# M650X.net
KiCad netlist of a schematic drawn in EAGLE
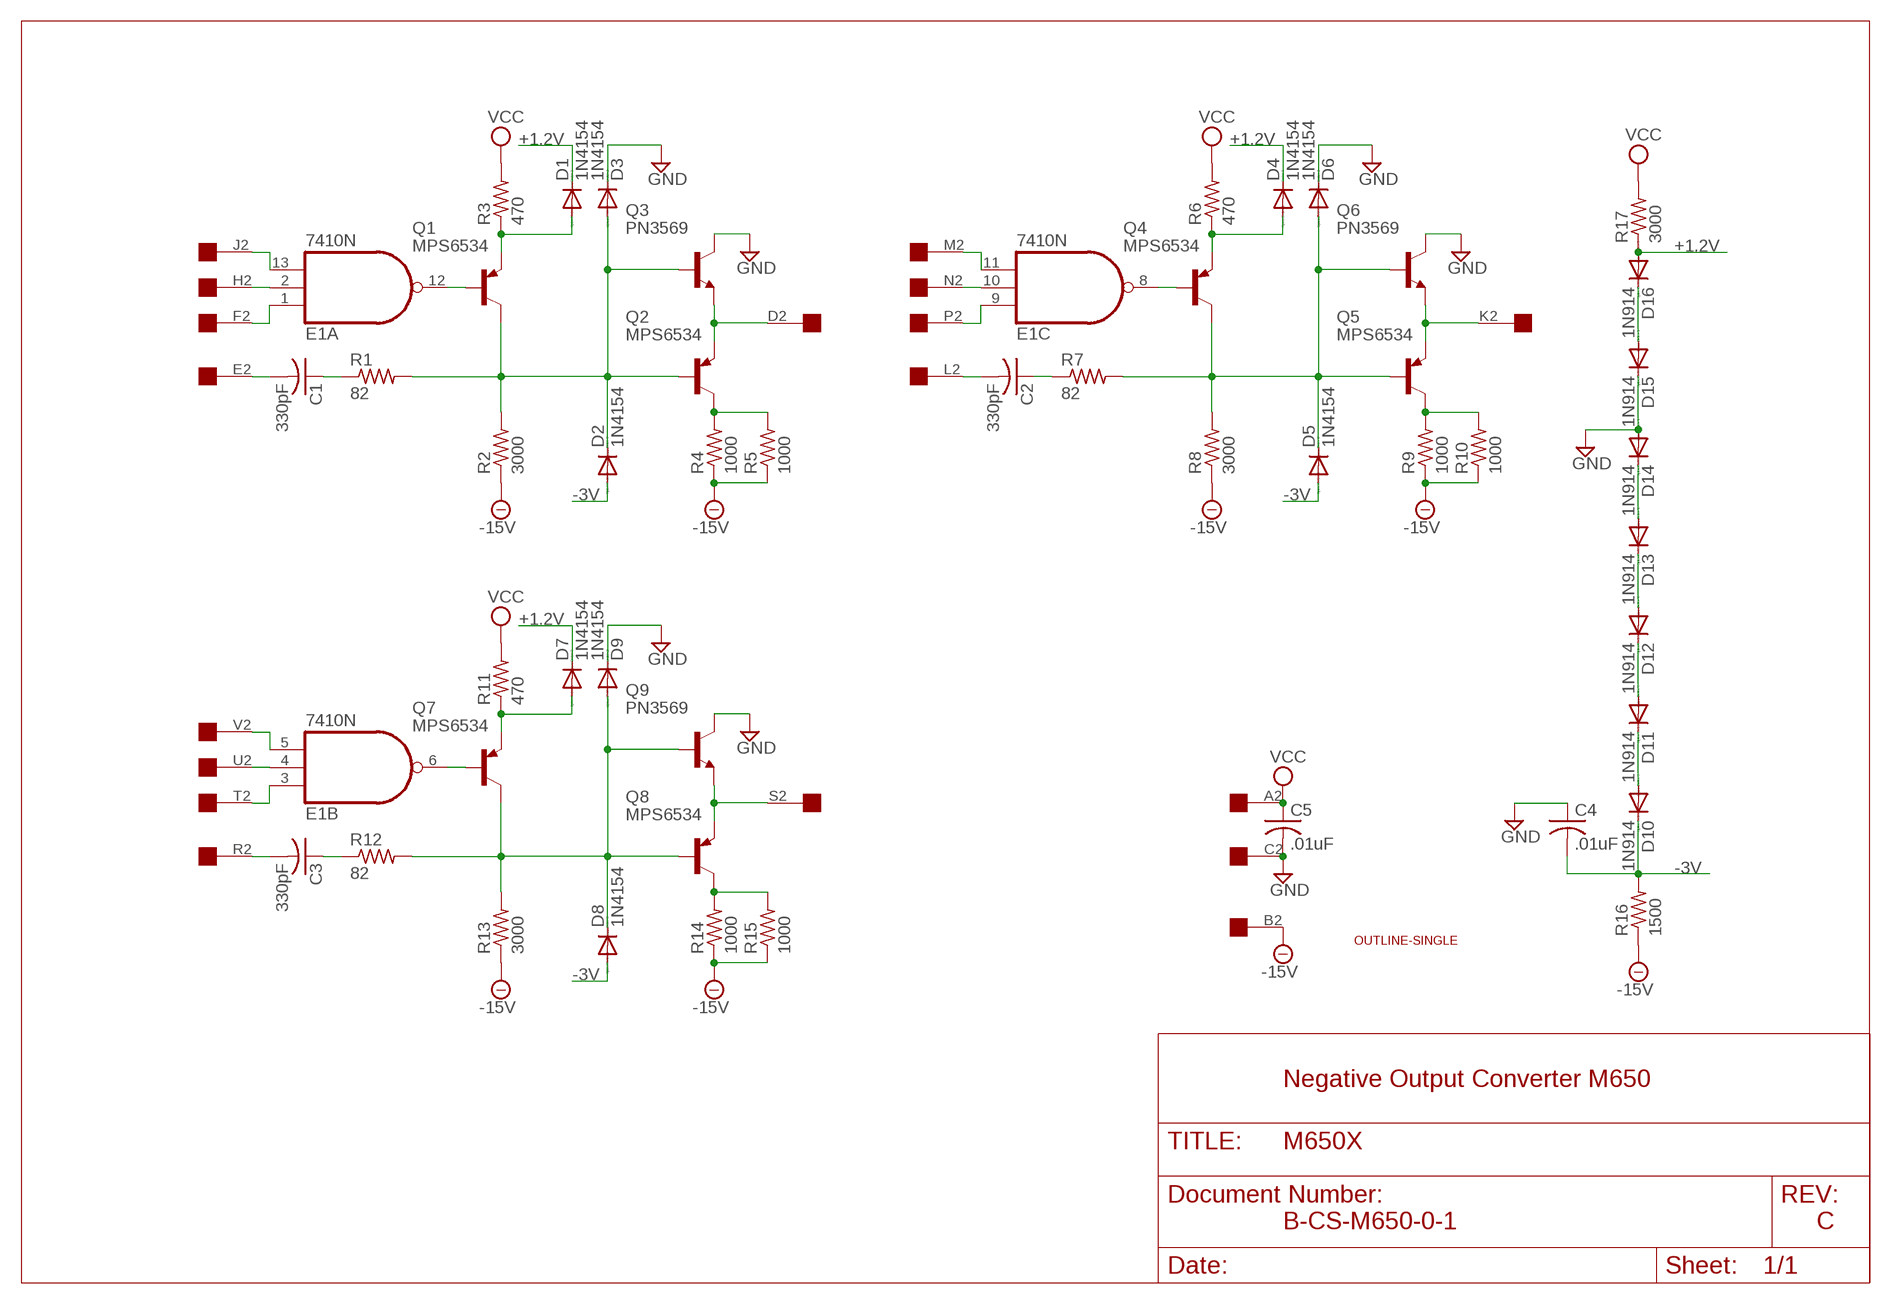
[diagram p0: schematic, sheet 1]

(export (version "E")
  (design (tool "Eeschema 10.0.6"))
  (components
    (comp (ref "C1")
      (value "330pF")
      (footprint "eagle-import:C050-025X075")
      (libsource (lib "eagle-import") (part "C-US050-025X075"))
    )
    (comp (ref "C2")
      (value "330pF")
      (footprint "eagle-import:C050-025X075")
      (libsource (lib "eagle-import") (part "C-US050-025X075"))
    )
    (comp (ref "C3")
      (value "330pF")
      (footprint "eagle-import:C050-025X075")
      (libsource (lib "eagle-import") (part "C-US050-025X075"))
    )
    (comp (ref "C4")
      (value ".01uF")
      (footprint "eagle-import:C050-025X075")
      (libsource (lib "eagle-import") (part "C-US050-025X075"))
    )
    (comp (ref "C5")
      (value ".01uF")
      (footprint "eagle-import:C050-025X075")
      (libsource (lib "eagle-import") (part "C-US050-025X075"))
    )
    (comp (ref "D1")
      (value "1N4154")
      (footprint "eagle-import:DO35-10")
      (libsource (lib "eagle-import") (part "1N4148DO35-10"))
    )
    (comp (ref "D2")
      (value "1N4154")
      (footprint "eagle-import:DO35-10")
      (libsource (lib "eagle-import") (part "1N4148DO35-10"))
    )
    (comp (ref "D3")
      (value "1N4154")
      (footprint "eagle-import:DO35-10")
      (libsource (lib "eagle-import") (part "1N4148DO35-10"))
    )
    (comp (ref "D4")
      (value "1N4154")
      (footprint "eagle-import:DO35-10")
      (libsource (lib "eagle-import") (part "1N4148DO35-10"))
    )
    (comp (ref "D5")
      (value "1N4154")
      (footprint "eagle-import:DO35-10")
      (libsource (lib "eagle-import") (part "1N4148DO35-10"))
    )
    (comp (ref "D6")
      (value "1N4154")
      (footprint "eagle-import:DO35-10")
      (libsource (lib "eagle-import") (part "1N4148DO35-10"))
    )
    (comp (ref "D7")
      (value "1N4154")
      (footprint "eagle-import:DO35-10")
      (libsource (lib "eagle-import") (part "1N4148DO35-10"))
    )
    (comp (ref "D8")
      (value "1N4154")
      (footprint "eagle-import:DO35-10")
      (libsource (lib "eagle-import") (part "1N4148DO35-10"))
    )
    (comp (ref "D9")
      (value "1N4154")
      (footprint "eagle-import:DO35-10")
      (libsource (lib "eagle-import") (part "1N4148DO35-10"))
    )
    (comp (ref "D10")
      (value "1N914")
      (footprint "eagle-import:DO35-10")
      (libsource (lib "eagle-import") (part "1N4148DO35-10"))
    )
    (comp (ref "D11")
      (value "1N914")
      (footprint "eagle-import:DO35-10")
      (libsource (lib "eagle-import") (part "1N4148DO35-10"))
    )
    (comp (ref "D12")
      (value "1N914")
      (footprint "eagle-import:DO35-10")
      (libsource (lib "eagle-import") (part "1N4148DO35-10"))
    )
    (comp (ref "D13")
      (value "1N914")
      (footprint "eagle-import:DO35-10")
      (libsource (lib "eagle-import") (part "1N4148DO35-10"))
    )
    (comp (ref "D14")
      (value "1N914")
      (footprint "eagle-import:DO35-10")
      (libsource (lib "eagle-import") (part "1N4148DO35-10"))
    )
    (comp (ref "D15")
      (value "1N914")
      (footprint "eagle-import:DO35-10")
      (libsource (lib "eagle-import") (part "1N4148DO35-10"))
    )
    (comp (ref "D16")
      (value "1N914")
      (footprint "eagle-import:DO35-10")
      (libsource (lib "eagle-import") (part "1N4148DO35-10"))
    )
    (comp (ref "E1")
      (value "7410N")
      (footprint "eagle-import:DIL14")
      (libsource (lib "eagle-import") (part "7410N"))
    )
    (comp (ref "Q1")
      (value "MPS6534")
      (footprint "eagle-import:TO39")
      (libsource (lib "eagle-import") (part "2N5415"))
    )
    (comp (ref "Q2")
      (value "MPS6534")
      (footprint "eagle-import:TO39")
      (libsource (lib "eagle-import") (part "2N5415"))
    )
    (comp (ref "Q3")
      (value "PN3569")
      (footprint "eagle-import:TO5")
      (libsource (lib "eagle-import") (part "2N2219"))
    )
    (comp (ref "Q4")
      (value "MPS6534")
      (footprint "eagle-import:TO39")
      (libsource (lib "eagle-import") (part "2N5415"))
    )
    (comp (ref "Q5")
      (value "MPS6534")
      (footprint "eagle-import:TO39")
      (libsource (lib "eagle-import") (part "2N5415"))
    )
    (comp (ref "Q6")
      (value "PN3569")
      (footprint "eagle-import:TO5")
      (libsource (lib "eagle-import") (part "2N2219"))
    )
    (comp (ref "Q7")
      (value "MPS6534")
      (footprint "eagle-import:TO39")
      (libsource (lib "eagle-import") (part "2N5415"))
    )
    (comp (ref "Q8")
      (value "MPS6534")
      (footprint "eagle-import:TO39")
      (libsource (lib "eagle-import") (part "2N5415"))
    )
    (comp (ref "Q9")
      (value "PN3569")
      (footprint "eagle-import:TO5")
      (libsource (lib "eagle-import") (part "2N2219"))
    )
    (comp (ref "R1")
      (value "82")
      (footprint "eagle-import:0207_10")
      (libsource (lib "eagle-import") (part "R-US_0207/10"))
    )
    (comp (ref "R2")
      (value "3000")
      (footprint "eagle-import:0207_10")
      (libsource (lib "eagle-import") (part "R-US_0207/10"))
    )
    (comp (ref "R3")
      (value "470")
      (footprint "eagle-import:0207_10")
      (libsource (lib "eagle-import") (part "R-US_0207/10"))
    )
    (comp (ref "R4")
      (value "1000")
      (footprint "eagle-import:0207_10")
      (libsource (lib "eagle-import") (part "R-US_0207/10"))
    )
    (comp (ref "R5")
      (value "1000")
      (footprint "eagle-import:0207_10")
      (libsource (lib "eagle-import") (part "R-US_0207/10"))
    )
    (comp (ref "R6")
      (value "470")
      (footprint "eagle-import:0207_10")
      (libsource (lib "eagle-import") (part "R-US_0207/10"))
    )
    (comp (ref "R7")
      (value "82")
      (footprint "eagle-import:0207_10")
      (libsource (lib "eagle-import") (part "R-US_0207/10"))
    )
    (comp (ref "R8")
      (value "3000")
      (footprint "eagle-import:0207_10")
      (libsource (lib "eagle-import") (part "R-US_0207/10"))
    )
    (comp (ref "R9")
      (value "1000")
      (footprint "eagle-import:0207_10")
      (libsource (lib "eagle-import") (part "R-US_0207/10"))
    )
    (comp (ref "R10")
      (value "1000")
      (footprint "eagle-import:0207_10")
      (libsource (lib "eagle-import") (part "R-US_0207/10"))
    )
    (comp (ref "R11")
      (value "470")
      (footprint "eagle-import:0207_10")
      (libsource (lib "eagle-import") (part "R-US_0207/10"))
    )
    (comp (ref "R12")
      (value "82")
      (footprint "eagle-import:0207_10")
      (libsource (lib "eagle-import") (part "R-US_0207/10"))
    )
    (comp (ref "R13")
      (value "3000")
      (footprint "eagle-import:0207_10")
      (libsource (lib "eagle-import") (part "R-US_0207/10"))
    )
    (comp (ref "R14")
      (value "1000")
      (footprint "eagle-import:0207_10")
      (libsource (lib "eagle-import") (part "R-US_0207/10"))
    )
    (comp (ref "R15")
      (value "1000")
      (footprint "eagle-import:0207_10")
      (libsource (lib "eagle-import") (part "R-US_0207/10"))
    )
    (comp (ref "R16")
      (value "1500")
      (footprint "eagle-import:0207_10")
      (libsource (lib "eagle-import") (part "R-US_0207/10"))
    )
    (comp (ref "R17")
      (value "3000")
      (footprint "eagle-import:0207_10")
      (libsource (lib "eagle-import") (part "R-US_0207/10"))
    )
    (comp (ref "U$1")
      (value "OUTLINE-SINGLE")
      (footprint "eagle-import:SINGLE")
      (libsource (lib "eagle-import") (part "OUTLINE-SINGLE"))
    )
    (comp (ref "U$3")
      (value "EDGE-1")
      (footprint "eagle-import:EDGE-CON1")
      (libsource (lib "eagle-import") (part "EDGE-1"))
    )
  )
  (nets
    (net (code "1") (name "-15V") (class "Default")
      (node (ref "R10") (pin "1") (pinfunction "1_1") (pintype "passive"))
      (node (ref "R13") (pin "1") (pinfunction "1_1") (pintype "passive"))
      (node (ref "R14") (pin "1") (pinfunction "1_1") (pintype "passive"))
      (node (ref "R15") (pin "1") (pinfunction "1_1") (pintype "passive"))
      (node (ref "R16") (pin "1") (pinfunction "1_1") (pintype "passive"))
      (node (ref "R2") (pin "1") (pinfunction "1_1") (pintype "passive"))
      (node (ref "R4") (pin "1") (pinfunction "1_1") (pintype "passive"))
      (node (ref "R5") (pin "1") (pinfunction "1_1") (pintype "passive"))
      (node (ref "R8") (pin "1") (pinfunction "1_1") (pintype "passive"))
      (node (ref "R9") (pin "1") (pinfunction "1_1") (pintype "passive"))
      (node (ref "U$3") (pin "B2") (pinfunction "1_B2") (pintype "bidirectional"))
    )
    (net (code "2") (name "/+1.2V") (class "Default")
      (node (ref "D1") (pin "C") (pinfunction "C_C") (pintype "passive"))
      (node (ref "D16") (pin "A") (pinfunction "A_A") (pintype "passive"))
      (node (ref "D4") (pin "C") (pinfunction "C_C") (pintype "passive"))
      (node (ref "D7") (pin "C") (pinfunction "C_C") (pintype "passive"))
      (node (ref "R17") (pin "1") (pinfunction "1_1") (pintype "passive"))
    )
    (net (code "3") (name "/-3V") (class "Default")
      (node (ref "C4") (pin "2") (pinfunction "2_2") (pintype "passive"))
      (node (ref "D10") (pin "C") (pinfunction "C_C") (pintype "passive"))
      (node (ref "D2") (pin "A") (pinfunction "A_A") (pintype "passive"))
      (node (ref "D5") (pin "A") (pinfunction "A_A") (pintype "passive"))
      (node (ref "D8") (pin "A") (pinfunction "A_A") (pintype "passive"))
      (node (ref "R16") (pin "2") (pinfunction "2_2") (pintype "passive"))
    )
    (net (code "4") (name "GND") (class "Default")
      (node (ref "C4") (pin "1") (pinfunction "1_1") (pintype "passive"))
      (node (ref "C5") (pin "2") (pinfunction "2_2") (pintype "passive"))
      (node (ref "D14") (pin "A") (pinfunction "A_A") (pintype "passive"))
      (node (ref "D15") (pin "C") (pinfunction "C_C") (pintype "passive"))
      (node (ref "D3") (pin "C") (pinfunction "C_C") (pintype "passive"))
      (node (ref "D6") (pin "C") (pinfunction "C_C") (pintype "passive"))
      (node (ref "D9") (pin "C") (pinfunction "C_C") (pintype "passive"))
      (node (ref "Q3") (pin "3") (pinfunction "C_3") (pintype "passive"))
      (node (ref "Q6") (pin "3") (pinfunction "C_3") (pintype "passive"))
      (node (ref "Q9") (pin "3") (pinfunction "C_3") (pintype "passive"))
      (node (ref "U$3") (pin "C2") (pinfunction "1_C2") (pintype "bidirectional"))
    )
    (net (code "5") (name "Net-(C1-Pad1)") (class "Default")
      (node (ref "C1") (pin "1") (pinfunction "1_1") (pintype "passive"))
      (node (ref "R1") (pin "1") (pinfunction "1_1") (pintype "passive"))
    )
    (net (code "6") (name "Net-(C2-Pad1)") (class "Default")
      (node (ref "C2") (pin "1") (pinfunction "1_1") (pintype "passive"))
      (node (ref "R7") (pin "1") (pinfunction "1_1") (pintype "passive"))
    )
    (net (code "7") (name "Net-(C3-Pad1)") (class "Default")
      (node (ref "C3") (pin "1") (pinfunction "1_1") (pintype "passive"))
      (node (ref "R12") (pin "1") (pinfunction "1_1") (pintype "passive"))
    )
    (net (code "8") (name "Net-(D10-PadA)") (class "Default")
      (node (ref "D10") (pin "A") (pinfunction "A_A") (pintype "passive"))
      (node (ref "D11") (pin "C") (pinfunction "C_C") (pintype "passive"))
    )
    (net (code "9") (name "Net-(D11-PadA)") (class "Default")
      (node (ref "D11") (pin "A") (pinfunction "A_A") (pintype "passive"))
      (node (ref "D12") (pin "C") (pinfunction "C_C") (pintype "passive"))
    )
    (net (code "10") (name "Net-(D12-PadA)") (class "Default")
      (node (ref "D12") (pin "A") (pinfunction "A_A") (pintype "passive"))
      (node (ref "D13") (pin "C") (pinfunction "C_C") (pintype "passive"))
    )
    (net (code "11") (name "Net-(D13-PadA)") (class "Default")
      (node (ref "D13") (pin "A") (pinfunction "A_A") (pintype "passive"))
      (node (ref "D14") (pin "C") (pinfunction "C_C") (pintype "passive"))
    )
    (net (code "12") (name "Net-(D15-PadA)") (class "Default")
      (node (ref "D15") (pin "A") (pinfunction "A_A") (pintype "passive"))
      (node (ref "D16") (pin "C") (pinfunction "C_C") (pintype "passive"))
    )
    (net (code "13") (name "Net-(E1A-I0)") (class "Default")
      (node (ref "E1") (pin "1") (pinfunction "I0_1") (pintype "input"))
      (node (ref "U$3") (pin "F2") (pinfunction "1_F2") (pintype "bidirectional"))
    )
    (net (code "14") (name "Net-(E1A-I1)") (class "Default")
      (node (ref "E1") (pin "2") (pinfunction "I1_2") (pintype "input"))
      (node (ref "U$3") (pin "H2") (pinfunction "1_H2") (pintype "bidirectional"))
    )
    (net (code "15") (name "Net-(E1A-I2)") (class "Default")
      (node (ref "E1") (pin "13") (pinfunction "I2_13") (pintype "input"))
      (node (ref "U$3") (pin "J2") (pinfunction "1_J2") (pintype "bidirectional"))
    )
    (net (code "16") (name "Net-(E1A-O)") (class "Default")
      (node (ref "E1") (pin "12") (pinfunction "O_12") (pintype "output"))
      (node (ref "Q1") (pin "2") (pinfunction "B_2") (pintype "passive"))
    )
    (net (code "17") (name "Net-(E1B-I0)") (class "Default")
      (node (ref "E1") (pin "3") (pinfunction "I0_3") (pintype "input"))
      (node (ref "U$3") (pin "T2") (pinfunction "1_T2") (pintype "bidirectional"))
    )
    (net (code "18") (name "Net-(E1B-I1)") (class "Default")
      (node (ref "E1") (pin "4") (pinfunction "I1_4") (pintype "input"))
      (node (ref "U$3") (pin "U2") (pinfunction "1_U2") (pintype "bidirectional"))
    )
    (net (code "19") (name "Net-(E1B-I2)") (class "Default")
      (node (ref "E1") (pin "5") (pinfunction "I2_5") (pintype "input"))
      (node (ref "U$3") (pin "V2") (pinfunction "1_V2") (pintype "bidirectional"))
    )
    (net (code "20") (name "Net-(E1B-O)") (class "Default")
      (node (ref "E1") (pin "6") (pinfunction "O_6") (pintype "output"))
      (node (ref "Q7") (pin "2") (pinfunction "B_2") (pintype "passive"))
    )
    (net (code "21") (name "Net-(E1C-I0)") (class "Default")
      (node (ref "E1") (pin "9") (pinfunction "I0_9") (pintype "input"))
      (node (ref "U$3") (pin "P2") (pinfunction "1_P2") (pintype "bidirectional"))
    )
    (net (code "22") (name "Net-(E1C-I1)") (class "Default")
      (node (ref "E1") (pin "10") (pinfunction "I1_10") (pintype "input"))
      (node (ref "U$3") (pin "N2") (pinfunction "1_N2") (pintype "bidirectional"))
    )
    (net (code "23") (name "Net-(E1C-I2)") (class "Default")
      (node (ref "E1") (pin "11") (pinfunction "I2_11") (pintype "input"))
      (node (ref "U$3") (pin "M2") (pinfunction "1_M2") (pintype "bidirectional"))
    )
    (net (code "24") (name "Net-(E1C-O)") (class "Default")
      (node (ref "E1") (pin "8") (pinfunction "O_8") (pintype "output"))
      (node (ref "Q4") (pin "2") (pinfunction "B_2") (pintype "passive"))
    )
    (net (code "25") (name "Net-(Q1-C)") (class "Default")
      (node (ref "D2") (pin "C") (pinfunction "C_C") (pintype "passive"))
      (node (ref "D3") (pin "A") (pinfunction "A_A") (pintype "passive"))
      (node (ref "Q1") (pin "3") (pinfunction "C_3") (pintype "passive"))
      (node (ref "Q2") (pin "2") (pinfunction "B_2") (pintype "passive"))
      (node (ref "Q3") (pin "2") (pinfunction "B_2") (pintype "passive"))
      (node (ref "R1") (pin "2") (pinfunction "2_2") (pintype "passive"))
      (node (ref "R2") (pin "2") (pinfunction "2_2") (pintype "passive"))
    )
    (net (code "26") (name "Net-(Q1-E)") (class "Default")
      (node (ref "D1") (pin "A") (pinfunction "A_A") (pintype "passive"))
      (node (ref "Q1") (pin "1") (pinfunction "E_1") (pintype "passive"))
      (node (ref "R3") (pin "1") (pinfunction "1_1") (pintype "passive"))
    )
    (net (code "27") (name "Net-(Q2-C)") (class "Default")
      (node (ref "Q2") (pin "3") (pinfunction "C_3") (pintype "passive"))
      (node (ref "R4") (pin "2") (pinfunction "2_2") (pintype "passive"))
      (node (ref "R5") (pin "2") (pinfunction "2_2") (pintype "passive"))
    )
    (net (code "28") (name "Net-(Q2-E)") (class "Default")
      (node (ref "Q2") (pin "1") (pinfunction "E_1") (pintype "passive"))
      (node (ref "Q3") (pin "1") (pinfunction "E_1") (pintype "passive"))
      (node (ref "U$3") (pin "D2") (pinfunction "1_D2") (pintype "bidirectional"))
    )
    (net (code "29") (name "Net-(Q4-C)") (class "Default")
      (node (ref "D5") (pin "C") (pinfunction "C_C") (pintype "passive"))
      (node (ref "D6") (pin "A") (pinfunction "A_A") (pintype "passive"))
      (node (ref "Q4") (pin "3") (pinfunction "C_3") (pintype "passive"))
      (node (ref "Q5") (pin "2") (pinfunction "B_2") (pintype "passive"))
      (node (ref "Q6") (pin "2") (pinfunction "B_2") (pintype "passive"))
      (node (ref "R7") (pin "2") (pinfunction "2_2") (pintype "passive"))
      (node (ref "R8") (pin "2") (pinfunction "2_2") (pintype "passive"))
    )
    (net (code "30") (name "Net-(Q4-E)") (class "Default")
      (node (ref "D4") (pin "A") (pinfunction "A_A") (pintype "passive"))
      (node (ref "Q4") (pin "1") (pinfunction "E_1") (pintype "passive"))
      (node (ref "R6") (pin "1") (pinfunction "1_1") (pintype "passive"))
    )
    (net (code "31") (name "Net-(Q5-C)") (class "Default")
      (node (ref "Q5") (pin "3") (pinfunction "C_3") (pintype "passive"))
      (node (ref "R10") (pin "2") (pinfunction "2_2") (pintype "passive"))
      (node (ref "R9") (pin "2") (pinfunction "2_2") (pintype "passive"))
    )
    (net (code "32") (name "Net-(Q5-E)") (class "Default")
      (node (ref "Q5") (pin "1") (pinfunction "E_1") (pintype "passive"))
      (node (ref "Q6") (pin "1") (pinfunction "E_1") (pintype "passive"))
      (node (ref "U$3") (pin "K2") (pinfunction "1_K2") (pintype "bidirectional"))
    )
    (net (code "33") (name "Net-(Q7-C)") (class "Default")
      (node (ref "D8") (pin "C") (pinfunction "C_C") (pintype "passive"))
      (node (ref "D9") (pin "A") (pinfunction "A_A") (pintype "passive"))
      (node (ref "Q7") (pin "3") (pinfunction "C_3") (pintype "passive"))
      (node (ref "Q8") (pin "2") (pinfunction "B_2") (pintype "passive"))
      (node (ref "Q9") (pin "2") (pinfunction "B_2") (pintype "passive"))
      (node (ref "R12") (pin "2") (pinfunction "2_2") (pintype "passive"))
      (node (ref "R13") (pin "2") (pinfunction "2_2") (pintype "passive"))
    )
    (net (code "34") (name "Net-(Q7-E)") (class "Default")
      (node (ref "D7") (pin "A") (pinfunction "A_A") (pintype "passive"))
      (node (ref "Q7") (pin "1") (pinfunction "E_1") (pintype "passive"))
      (node (ref "R11") (pin "1") (pinfunction "1_1") (pintype "passive"))
    )
    (net (code "35") (name "Net-(Q8-C)") (class "Default")
      (node (ref "Q8") (pin "3") (pinfunction "C_3") (pintype "passive"))
      (node (ref "R14") (pin "2") (pinfunction "2_2") (pintype "passive"))
      (node (ref "R15") (pin "2") (pinfunction "2_2") (pintype "passive"))
    )
    (net (code "36") (name "Net-(Q8-E)") (class "Default")
      (node (ref "Q8") (pin "1") (pinfunction "E_1") (pintype "passive"))
      (node (ref "Q9") (pin "1") (pinfunction "E_1") (pintype "passive"))
      (node (ref "U$3") (pin "S2") (pinfunction "1_S2") (pintype "bidirectional"))
    )
    (net (code "37") (name "Net-(U$3E-1)") (class "Default")
      (node (ref "C1") (pin "2") (pinfunction "2_2") (pintype "passive"))
      (node (ref "U$3") (pin "E2") (pinfunction "1_E2") (pintype "bidirectional"))
    )
    (net (code "38") (name "Net-(U$3J-1)") (class "Default")
      (node (ref "C2") (pin "2") (pinfunction "2_2") (pintype "passive"))
      (node (ref "U$3") (pin "L2") (pinfunction "1_L2") (pintype "bidirectional"))
    )
    (net (code "39") (name "Net-(U$3N-1)") (class "Default")
      (node (ref "C3") (pin "2") (pinfunction "2_2") (pintype "passive"))
      (node (ref "U$3") (pin "R2") (pinfunction "1_R2") (pintype "bidirectional"))
    )
    (net (code "40") (name "VCC") (class "Default")
      (node (ref "C5") (pin "1") (pinfunction "1_1") (pintype "passive"))
      (node (ref "R11") (pin "2") (pinfunction "2_2") (pintype "passive"))
      (node (ref "R17") (pin "2") (pinfunction "2_2") (pintype "passive"))
      (node (ref "R3") (pin "2") (pinfunction "2_2") (pintype "passive"))
      (node (ref "R6") (pin "2") (pinfunction "2_2") (pintype "passive"))
      (node (ref "U$3") (pin "A2") (pinfunction "1_A2") (pintype "bidirectional"))
    )
  )
)
